# TXTempus.net
KiCad netlist of a schematic drawn in EAGLE
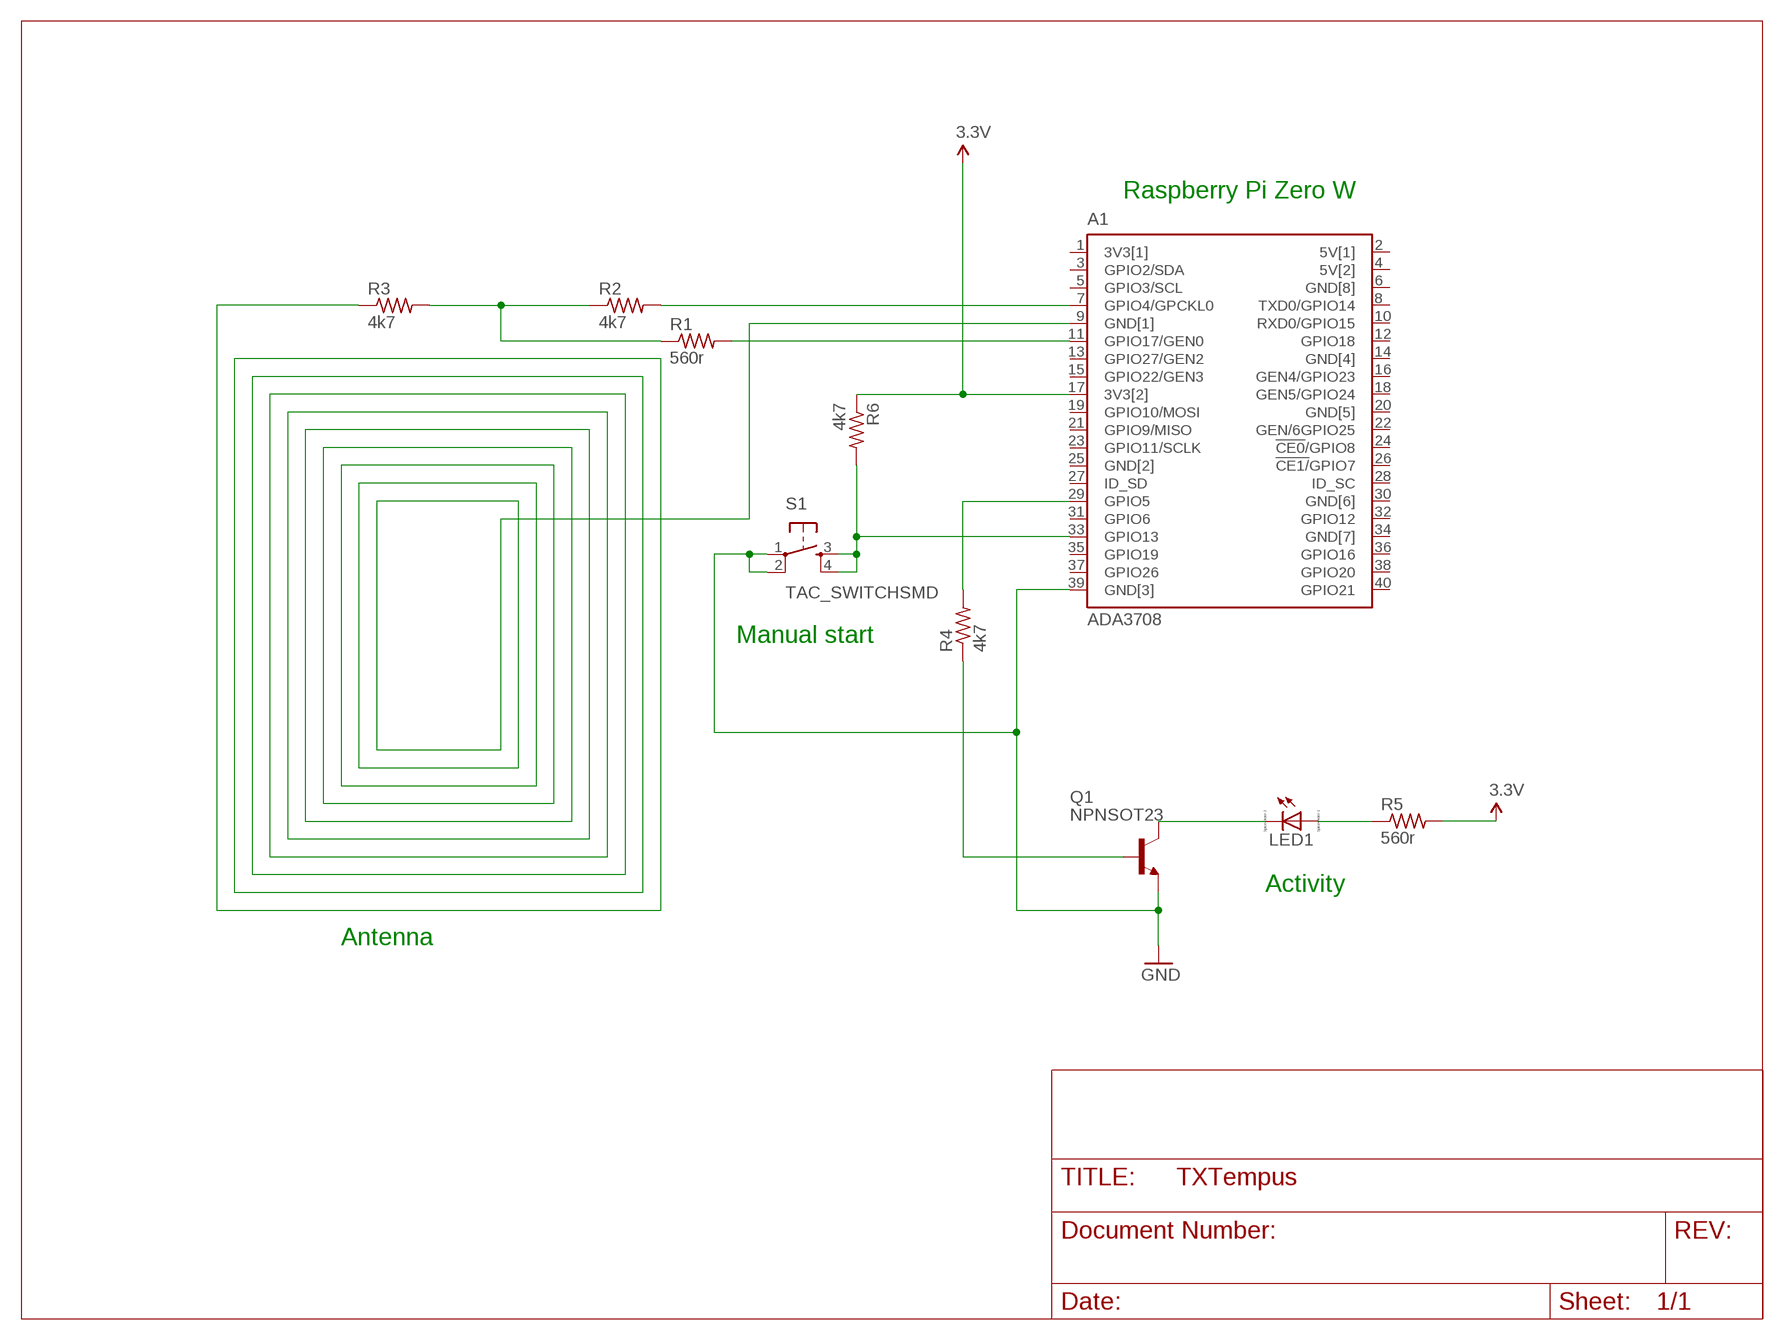
[diagram p0: schematic, sheet 1]

(export (version "E")
  (design (tool "Eeschema 10.0.6"))
  (components
    (comp (ref "A1")
      (value "ADA3708")
      (footprint "eagle-import:ADA3708_RPI-ZERO")
      (fields (field (name "MF") "Raspberry Pi"))
      (libsource (lib "eagle-import") (part "ADA3708"))
    )
    (comp (ref "LED1")
      (value "LED_E")
      (footprint "eagle-import:LED_1206")
      (libsource (lib "eagle-import") (part "LED_E"))
    )
    (comp (ref "Q1")
      (value "NPNSOT23")
      (footprint "eagle-import:SOT23")
      (libsource (lib "eagle-import") (part "NPNSOT23"))
    )
    (comp (ref "R1")
      (value "560r")
      (footprint "eagle-import:M0805")
      (libsource (lib "eagle-import") (part "R-US_M0805"))
    )
    (comp (ref "R2")
      (value "4k7")
      (footprint "eagle-import:M0805")
      (libsource (lib "eagle-import") (part "R-US_M0805"))
    )
    (comp (ref "R3")
      (value "4k7")
      (footprint "eagle-import:M0805")
      (libsource (lib "eagle-import") (part "R-US_M0805"))
    )
    (comp (ref "R4")
      (value "4k7")
      (footprint "eagle-import:M0805")
      (libsource (lib "eagle-import") (part "R-US_M0805"))
    )
    (comp (ref "R5")
      (value "560r")
      (footprint "eagle-import:M0805")
      (libsource (lib "eagle-import") (part "R-US_M0805"))
    )
    (comp (ref "R6")
      (value "4k7")
      (footprint "eagle-import:M0805")
      (libsource (lib "eagle-import") (part "R-US_M0805"))
    )
    (comp (ref "S1")
      (value "TAC_SWITCHSMD")
      (footprint "eagle-import:TACTILE-SWITCH-SMD")
      (libsource (lib "eagle-import") (part "TAC_SWITCHSMD"))
    )
  )
  (nets
    (net (code "1") (name "/3V3[1]") (class "Default")
      (node (ref "A1") (pin "1") (pinfunction "3V3[1]_1") (pintype "power_in"))
    )
    (net (code "2") (name "/5V[1]") (class "Default")
      (node (ref "A1") (pin "2") (pinfunction "5V[1]_2") (pintype "power_in"))
    )
    (net (code "3") (name "/5V[2]") (class "Default")
      (node (ref "A1") (pin "4") (pinfunction "5V[2]_4") (pintype "power_in"))
    )
    (net (code "4") (name "/GND[2]") (class "Default")
      (node (ref "A1") (pin "25") (pinfunction "GND[2]_25") (pintype "power_in"))
    )
    (net (code "5") (name "/GND[4]") (class "Default")
      (node (ref "A1") (pin "14") (pinfunction "GND[4]_14") (pintype "power_in"))
    )
    (net (code "6") (name "/GND[5]") (class "Default")
      (node (ref "A1") (pin "20") (pinfunction "GND[5]_20") (pintype "power_in"))
    )
    (net (code "7") (name "/GND[6]") (class "Default")
      (node (ref "A1") (pin "30") (pinfunction "GND[6]_30") (pintype "power_in"))
    )
    (net (code "8") (name "/GND[7]") (class "Default")
      (node (ref "A1") (pin "34") (pinfunction "GND[7]_34") (pintype "power_in"))
    )
    (net (code "9") (name "/GND[8]") (class "Default")
      (node (ref "A1") (pin "6") (pinfunction "GND[8]_6") (pintype "power_in"))
    )
    (net (code "10") (name "3.3V") (class "Default")
      (node (ref "A1") (pin "17") (pinfunction "3V3[2]_17") (pintype "power_in"))
      (node (ref "R5") (pin "2") (pinfunction "2_2") (pintype "passive"))
      (node (ref "R6") (pin "1") (pinfunction "1_1") (pintype "passive"))
    )
    (net (code "11") (name "GND") (class "Default")
      (node (ref "A1") (pin "39") (pinfunction "GND[3]_39") (pintype "power_in"))
      (node (ref "Q1") (pin "2") (pinfunction "E_2") (pintype "passive"))
      (node (ref "S1") (pin "1") (pinfunction "1_1") (pintype "passive"))
      (node (ref "S1") (pin "2") (pinfunction "2_2") (pintype "passive"))
    )
    (net (code "12") (name "Net-(A1-GND[1])") (class "Default")
      (node (ref "A1") (pin "9") (pinfunction "GND[1]_9") (pintype "power_in"))
      (node (ref "R3") (pin "1") (pinfunction "1_1") (pintype "passive"))
    )
    (net (code "13") (name "Net-(A1-GPIO4{slash}GPCKL0)") (class "Default")
      (node (ref "A1") (pin "7") (pinfunction "GPIO4/GPCKL0_7") (pintype "bidirectional"))
      (node (ref "R2") (pin "2") (pinfunction "2_2") (pintype "passive"))
    )
    (net (code "14") (name "Net-(A1-GPIO5)") (class "Default")
      (node (ref "A1") (pin "29") (pinfunction "GPIO5_29") (pintype "bidirectional"))
      (node (ref "R4") (pin "2") (pinfunction "2_2") (pintype "passive"))
    )
    (net (code "15") (name "Net-(A1-GPIO13)") (class "Default")
      (node (ref "A1") (pin "33") (pinfunction "GPIO13_33") (pintype "bidirectional"))
      (node (ref "R6") (pin "2") (pinfunction "2_2") (pintype "passive"))
      (node (ref "S1") (pin "3") (pinfunction "3_3") (pintype "passive"))
      (node (ref "S1") (pin "4") (pinfunction "4_4") (pintype "passive"))
    )
    (net (code "16") (name "Net-(A1-GPIO17{slash}GEN0)") (class "Default")
      (node (ref "A1") (pin "11") (pinfunction "GPIO17/GEN0_11") (pintype "bidirectional"))
      (node (ref "R1") (pin "2") (pinfunction "2_2") (pintype "passive"))
    )
    (net (code "17") (name "Net-(LED1-PadA)") (class "Default")
      (node (ref "LED1") (pin "A") (pinfunction "A_A") (pintype "passive"))
      (node (ref "R5") (pin "1") (pinfunction "1_1") (pintype "passive"))
    )
    (net (code "18") (name "Net-(Q1-B)") (class "Default")
      (node (ref "Q1") (pin "1") (pinfunction "B_1") (pintype "passive"))
      (node (ref "R4") (pin "1") (pinfunction "1_1") (pintype "passive"))
    )
    (net (code "19") (name "Net-(Q1-C)") (class "Default")
      (node (ref "LED1") (pin "C") (pinfunction "C_C") (pintype "passive"))
      (node (ref "Q1") (pin "3") (pinfunction "C_3") (pintype "passive"))
    )
    (net (code "20") (name "Net-(R1-Pad1)") (class "Default")
      (node (ref "R1") (pin "1") (pinfunction "1_1") (pintype "passive"))
      (node (ref "R2") (pin "1") (pinfunction "1_1") (pintype "passive"))
      (node (ref "R3") (pin "2") (pinfunction "2_2") (pintype "passive"))
    )
    (net (code "21") (name "unconnected-(A1-GEN4{slash}GPIO23-Pad16)") (class "Default")
      (node (ref "A1") (pin "16") (pinfunction "GEN4/GPIO23_16") (pintype "bidirectional"))
    )
    (net (code "22") (name "unconnected-(A1-GEN5{slash}GPIO24-Pad18)") (class "Default")
      (node (ref "A1") (pin "18") (pinfunction "GEN5/GPIO24_18") (pintype "bidirectional"))
    )
    (net (code "23") (name "unconnected-(A1-GEN{slash}6GPIO25-Pad22)") (class "Default")
      (node (ref "A1") (pin "22") (pinfunction "GEN/6GPIO25_22") (pintype "bidirectional"))
    )
    (net (code "24") (name "unconnected-(A1-GPIO2{slash}SDA-Pad3)") (class "Default")
      (node (ref "A1") (pin "3") (pinfunction "GPIO2/SDA_3") (pintype "bidirectional"))
    )
    (net (code "25") (name "unconnected-(A1-GPIO3{slash}SCL-Pad5)") (class "Default")
      (node (ref "A1") (pin "5") (pinfunction "GPIO3/SCL_5") (pintype "bidirectional"))
    )
    (net (code "26") (name "unconnected-(A1-GPIO6-Pad31)") (class "Default")
      (node (ref "A1") (pin "31") (pinfunction "GPIO6_31") (pintype "bidirectional"))
    )
    (net (code "27") (name "unconnected-(A1-GPIO9{slash}MISO-Pad21)") (class "Default")
      (node (ref "A1") (pin "21") (pinfunction "GPIO9/MISO_21") (pintype "bidirectional"))
    )
    (net (code "28") (name "unconnected-(A1-GPIO10{slash}MOSI-Pad19)") (class "Default")
      (node (ref "A1") (pin "19") (pinfunction "GPIO10/MOSI_19") (pintype "bidirectional"))
    )
    (net (code "29") (name "unconnected-(A1-GPIO11{slash}SCLK-Pad23)") (class "Default")
      (node (ref "A1") (pin "23") (pinfunction "GPIO11/SCLK_23") (pintype "bidirectional"))
    )
    (net (code "30") (name "unconnected-(A1-GPIO12-Pad32)") (class "Default")
      (node (ref "A1") (pin "32") (pinfunction "GPIO12_32") (pintype "bidirectional"))
    )
    (net (code "31") (name "unconnected-(A1-GPIO16-Pad36)") (class "Default")
      (node (ref "A1") (pin "36") (pinfunction "GPIO16_36") (pintype "bidirectional"))
    )
    (net (code "32") (name "unconnected-(A1-GPIO18-Pad12)") (class "Default")
      (node (ref "A1") (pin "12") (pinfunction "GPIO18_12") (pintype "bidirectional"))
    )
    (net (code "33") (name "unconnected-(A1-GPIO19-Pad35)") (class "Default")
      (node (ref "A1") (pin "35") (pinfunction "GPIO19_35") (pintype "bidirectional"))
    )
    (net (code "34") (name "unconnected-(A1-GPIO20-Pad38)") (class "Default")
      (node (ref "A1") (pin "38") (pinfunction "GPIO20_38") (pintype "bidirectional"))
    )
    (net (code "35") (name "unconnected-(A1-GPIO21-Pad40)") (class "Default")
      (node (ref "A1") (pin "40") (pinfunction "GPIO21_40") (pintype "bidirectional"))
    )
    (net (code "36") (name "unconnected-(A1-GPIO22{slash}GEN3-Pad15)") (class "Default")
      (node (ref "A1") (pin "15") (pinfunction "GPIO22/GEN3_15") (pintype "bidirectional"))
    )
    (net (code "37") (name "unconnected-(A1-GPIO26-Pad37)") (class "Default")
      (node (ref "A1") (pin "37") (pinfunction "GPIO26_37") (pintype "bidirectional"))
    )
    (net (code "38") (name "unconnected-(A1-GPIO27{slash}GEN2-Pad13)") (class "Default")
      (node (ref "A1") (pin "13") (pinfunction "GPIO27/GEN2_13") (pintype "bidirectional"))
    )
    (net (code "39") (name "unconnected-(A1-ID_SC-Pad28)") (class "Default")
      (node (ref "A1") (pin "28") (pinfunction "ID_SC_28") (pintype "bidirectional"))
    )
    (net (code "40") (name "unconnected-(A1-ID_SD-Pad27)") (class "Default")
      (node (ref "A1") (pin "27") (pinfunction "ID_SD_27") (pintype "bidirectional"))
    )
    (net (code "41") (name "unconnected-(A1-RXD0{slash}GPIO15-Pad10)") (class "Default")
      (node (ref "A1") (pin "10") (pinfunction "RXD0/GPIO15_10") (pintype "bidirectional"))
    )
    (net (code "42") (name "unconnected-(A1-TXD0{slash}GPIO14-Pad8)") (class "Default")
      (node (ref "A1") (pin "8") (pinfunction "TXD0/GPIO14_8") (pintype "bidirectional"))
    )
    (net (code "43") (name "unconnected-(A1-~{CE0}{slash}GPIO8-Pad24)") (class "Default")
      (node (ref "A1") (pin "24") (pinfunction "~{CE0}/GPIO8_24") (pintype "bidirectional"))
    )
    (net (code "44") (name "unconnected-(A1-~{CE1{slash}}GPIO7-Pad26)") (class "Default")
      (node (ref "A1") (pin "26") (pinfunction "~{CE1/}GPIO7_26") (pintype "bidirectional"))
    )
  )
)
